# Main_Power_Switch.net
KiCad netlist of a schematic drawn in Altium Designer
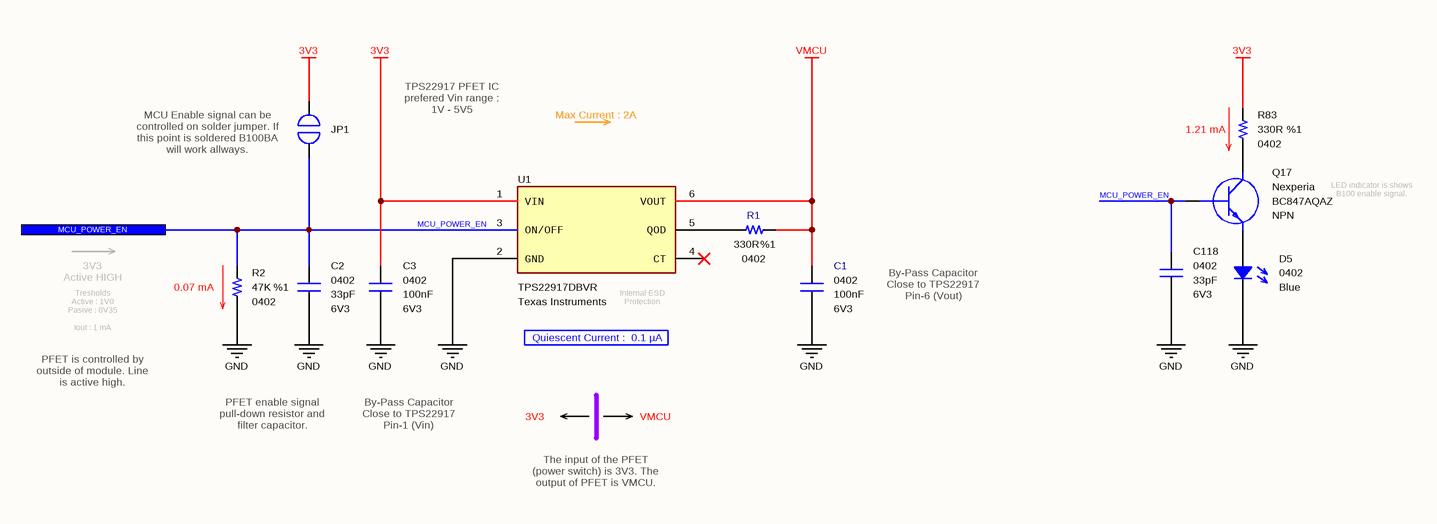
[diagram p0: Main Power Switch.SchDoc]

(export (version "E")
  (design (tool "Eeschema 10.0.6"))
  (components
    (comp (ref "C1")
      (value "100nF")
      (footprint "CAPACITOR_0402")
      (description "Capacitor - 100nF [0402-6V3] (Ceramic)")
      (fields
        (field (name "TOLERANCE") "%10")
        (field (name "CASE") "0402")
        (field (name "VOLTAGE") "6V3")
        (field (name "MANUFACTURER PART NUMBER") "04026D104KAT4A")
      )
      (libsource (lib "Ovoo_Library") (part "Capacitor - 100nF [0402-6V3]"))
    )
    (comp (ref "C2")
      (value "33pF")
      (footprint "CAPACITOR_0402")
      (description "Capacitor - 33pF [0402] (Ceramic)")
      (fields
        (field (name "TOLERANCE") "10%")
        (field (name "CASE") "0402")
        (field (name "VOLTAGE") "6V3")
        (field (name "MANUFACTURER PART NUMBER") "C0402C330J9RACAUTO")
      )
      (libsource (lib "Ovoo_Library") (part "Capacitor - 33pF [0402-6V3]"))
    )
    (comp (ref "C3")
      (value "100nF")
      (footprint "CAPACITOR_0402")
      (description "Capacitor - 100nF [0402-6V3] (Ceramic)")
      (fields
        (field (name "CASE") "0402")
        (field (name "TOLERANCE") "%10")
        (field (name "VOLTAGE") "6V3")
        (field (name "MANUFACTURER PART NUMBER") "04026D104KAT4A")
      )
      (libsource (lib "Ovoo_Library") (part "Capacitor - 100nF [0402-6V3]"))
    )
    (comp (ref "C118")
      (value "33pF")
      (footprint "CAPACITOR_0402")
      (description "Capacitor - 33pF [0402] (Ceramic)")
      (fields
        (field (name "CASE") "0402")
        (field (name "TOLERANCE") "10%")
        (field (name "VOLTAGE") "6V3")
        (field (name "MANUFACTURER PART NUMBER") "C0402C330J9RACAUTO")
      )
      (libsource (lib "Ovoo_Library") (part "Capacitor - 33pF [0402-6V3]"))
    )
    (comp (ref "D5")
      (value "SMD LED (Blue)")
      (footprint "LED_0402")
      (description "Standard LEDs - SMD PICOLEDTM;BLUE LED; 25M @ 5MA")
      (fields
        (field (name "CASE") "0402")
        (field (name "COLOR") "Blue")
        (field (name "MANUFACTURER PART NUMBER") "SMLP13BC8TT86")
        (field (name "MOUSER PART NUMBER") "755-SMLP13BC8TT86")
      )
      (libsource (lib "Ovoo_Library") (part "Diode - LED (0402-Blue)"))
    )
    (comp (ref "JP1")
      (value "Solder Jumper")
      (footprint "PCB_Solder_Jumper")
      (description "PCB Solder Jumper")
      (libsource (lib "Ovoo_Library") (part "PCB - Solder Jumper"))
    )
    (comp (ref "Q17")
      (value "BC847AQAZ")
      (footprint "SOT1215")
      (description "Bipolar NPN Transistors")
      (fields
        (field (name "POLARITY") "NPN")
        (field (name "MANUFACTURER NAME") "Nexperia")
        (field (name "MANUFACTURER PART NUMBER") "BC847AQAZ")
      )
      (libsource (lib "Ovoo_Library") (part "Transistor - BC847"))
    )
    (comp (ref "R1")
      (value "330R")
      (footprint "RESISTOR_0402")
      (description "Thick Film Resistors - SMD 1/16 W 330 Ohm 1%")
      (fields
        (field (name "TOLERANCE") "%1")
        (field (name "CASE") "0402")
        (field (name "MANUFACTURER PART NUMBER") "CRCW0402330RFKED")
        (field (name "MOUSER PART NUMBER") "71-CRCW0402-330-E3")
      )
      (libsource (lib "Ovoo_Library") (part "Resistor - 330R"))
    )
    (comp (ref "R2")
      (value "47K")
      (footprint "RESISTOR_0402")
      (description "Thick Film Resistors - SMD 1/16 W 47 Kohms 1%")
      (fields
        (field (name "TOLERANCE") "%1")
        (field (name "CASE") "0402")
        (field (name "MANUFACTURER PART NUMBER") "CRCW040247K0FKED")
        (field (name "Comment") "47K - 0402 - %1 - 1/16W")
      )
      (libsource (lib "Ovoo_Library") (part "Resistor - 47K"))
    )
    (comp (ref "R83")
      (value "330R")
      (footprint "RESISTOR_0402")
      (description "Thick Film Resistors - SMD 1/16 W 330 Ohm 1%")
      (fields
        (field (name "TOLERANCE") "%1")
        (field (name "CASE") "0402")
        (field (name "MANUFACTURER PART NUMBER") "CRCW0402330RFKED")
        (field (name "MOUSER PART NUMBER") "71-CRCW0402-330-E3")
      )
      (libsource (lib "Ovoo_Library") (part "Resistor - 330R"))
    )
    (comp (ref "U1")
      (value "Power Switch")
      (footprint "SOT-23-6")
      (description "Power Switch MosFet")
      (fields
        (field (name "MOUSER PART NUMBER") "595-TPS22917DBVR")
        (field (name "MANUFACTURER PART NUMBER") "TPS22917DBVR")
        (field (name "MANUFACTURER NAME") "Texas Instruments")
      )
      (libsource (lib "Ovoo_Library") (part "IC - TPS22917DBVR"))
    )
  )
  (nets
    (net (code "1") (name "/MCU_POWER_EN") (class "Default")
      (node (ref "C118") (pin "1") (pinfunction "1_1") (pintype "passive"))
      (node (ref "C2") (pin "2") (pinfunction "2_2") (pintype "passive"))
      (node (ref "JP1") (pin "1") (pinfunction "1_1") (pintype "passive"))
      (node (ref "Q17") (pin "1") (pinfunction "B_1") (pintype "passive"))
      (node (ref "R2") (pin "2") (pinfunction "2_2") (pintype "passive"))
      (node (ref "U1") (pin "3") (pinfunction "ON/OFF_3") (pintype "passive"))
    )
    (net (code "2") (name "3V3") (class "Default")
      (node (ref "C3") (pin "1") (pinfunction "1_1") (pintype "passive"))
      (node (ref "JP1") (pin "2") (pinfunction "2_2") (pintype "passive"))
      (node (ref "R83") (pin "2") (pinfunction "2_2") (pintype "passive"))
      (node (ref "U1") (pin "1") (pinfunction "VIN_1") (pintype "power_in"))
    )
    (net (code "3") (name "GND") (class "Default")
      (node (ref "C1") (pin "2") (pinfunction "2_2") (pintype "passive"))
      (node (ref "C118") (pin "2") (pinfunction "2_2") (pintype "passive"))
      (node (ref "C2") (pin "1") (pinfunction "1_1") (pintype "passive"))
      (node (ref "C3") (pin "2") (pinfunction "2_2") (pintype "passive"))
      (node (ref "D5") (pin "1") (pinfunction "1_1") (pintype "passive"))
      (node (ref "R2") (pin "1") (pinfunction "1_1") (pintype "passive"))
      (node (ref "U1") (pin "2") (pinfunction "GND_2") (pintype "power_in"))
    )
    (net (code "4") (name "Net-(Q17-C)") (class "Default")
      (node (ref "Q17") (pin "3") (pinfunction "C_3") (pintype "passive"))
      (node (ref "R83") (pin "1") (pinfunction "1_1") (pintype "passive"))
    )
    (net (code "5") (name "Net-(Q17-E)") (class "Default")
      (node (ref "D5") (pin "2") (pinfunction "2_2") (pintype "passive"))
      (node (ref "Q17") (pin "2") (pinfunction "E_2") (pintype "passive"))
    )
    (net (code "6") (name "Net-(U1-QOD)") (class "Default")
      (node (ref "R1") (pin "2") (pinfunction "2_2") (pintype "passive"))
      (node (ref "U1") (pin "5") (pinfunction "QOD_5") (pintype "power_in"))
    )
    (net (code "7") (name "VMCU") (class "Default")
      (node (ref "C1") (pin "1") (pinfunction "1_1") (pintype "passive"))
      (node (ref "R1") (pin "1") (pinfunction "1_1") (pintype "passive"))
      (node (ref "U1") (pin "6") (pinfunction "VOUT_6") (pintype "power_in"))
    )
    (net (code "8") (name "unconnected-(U1-CT-Pad4)") (class "Default")
      (node (ref "U1") (pin "4") (pinfunction "CT_4") (pintype "power_in+no_connect"))
    )
  )
)
